# Sheet2.net
KiCad netlist of a schematic drawn in Altium Designer
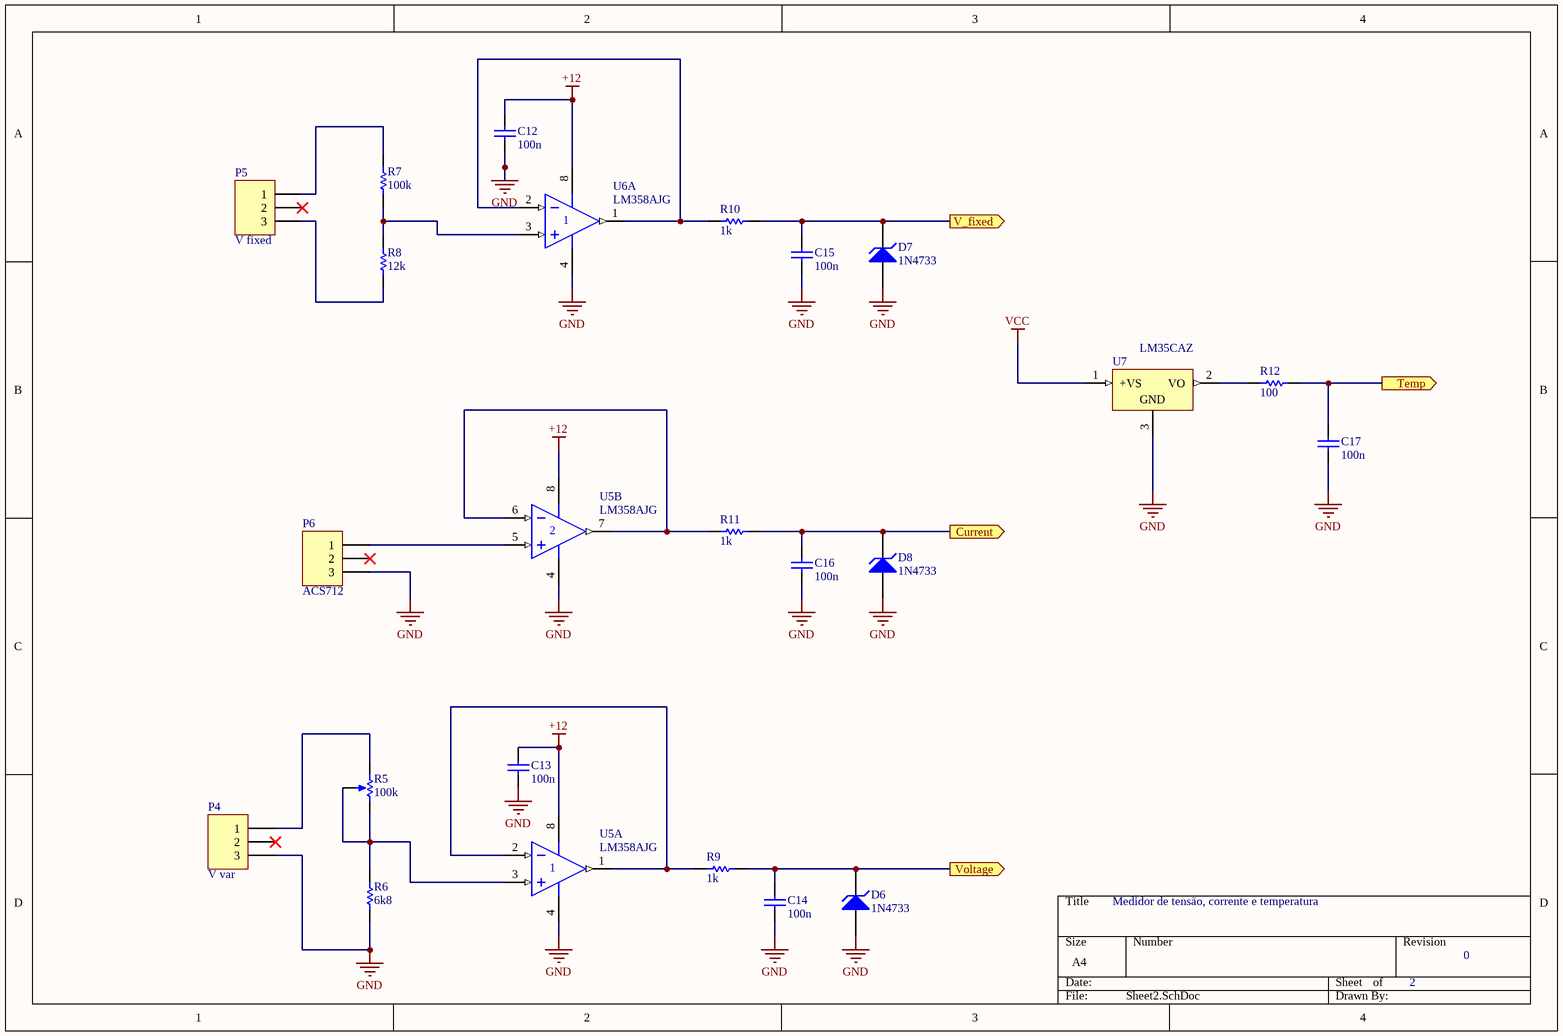
[diagram p0: Sheet2.SchDoc]

(export (version "E")
  (design (tool "Eeschema 10.0.6"))
  (components
    (comp (ref "C12")
      (value "100n")
      (footprint "RAD-0.2")
      (description "Capacitor")
      (libsource (lib "Basic Library") (part "C"))
    )
    (comp (ref "C13")
      (value "100n")
      (footprint "RAD-0.2")
      (description "Capacitor")
      (libsource (lib "Basic Library") (part "C"))
    )
    (comp (ref "C14")
      (value "100n")
      (footprint "RAD-0.2")
      (description "Capacitor")
      (libsource (lib "Basic Library") (part "C"))
    )
    (comp (ref "C15")
      (value "100n")
      (footprint "RAD-0.2")
      (description "Capacitor")
      (libsource (lib "Basic Library") (part "C"))
    )
    (comp (ref "C16")
      (value "100n")
      (footprint "RAD-0.2")
      (description "Capacitor")
      (libsource (lib "Basic Library") (part "C"))
    )
    (comp (ref "C17")
      (value "100n")
      (footprint "RAD-0.2")
      (description "Capacitor")
      (libsource (lib "Basic Library") (part "C"))
    )
    (comp (ref "D6")
      (value "1N4733")
      (footprint "DIODE-SIGNAL")
      (description "Zener Diode")
      (libsource (lib "Basic Library") (part "D Zener"))
    )
    (comp (ref "D7")
      (value "1N4733")
      (footprint "DIODE-SIGNAL")
      (description "Zener Diode")
      (libsource (lib "Basic Library") (part "D Zener"))
    )
    (comp (ref "D8")
      (value "1N4733")
      (footprint "DIODE-SIGNAL")
      (description "Zener Diode")
      (libsource (lib "Basic Library") (part "D Zener"))
    )
    (comp (ref "P4")
      (value "V var")
      (footprint "HDR1X3")
      (description "Header, 3-Pin")
      (fields (field (name "PUBLISHER") "Altium Limited"))
      (libsource (lib "Miscellaneous Connectors") (part "Header 3"))
    )
    (comp (ref "P5")
      (value "V fixed")
      (footprint "HDR1X3")
      (description "Header, 3-Pin")
      (fields (field (name "PUBLISHER") "Altium Limited"))
      (libsource (lib "Miscellaneous Connectors") (part "Header 3"))
    )
    (comp (ref "P6")
      (value "ACS712")
      (footprint "HDR1X3")
      (description "Header, 3-Pin")
      (fields (field (name "PUBLISHER") "Altium Limited"))
      (libsource (lib "Miscellaneous Connectors") (part "Header 3"))
    )
    (comp (ref "R5")
      (value "100k")
      (footprint "VR1")
      (description "Potentiometer")
      (libsource (lib "Basic Library") (part "R Pot"))
    )
    (comp (ref "R6")
      (value "6k8")
      (footprint "AXIAL-0.4")
      (description "Resistor")
      (libsource (lib "Basic Library") (part "R"))
    )
    (comp (ref "R7")
      (value "100k")
      (footprint "AXIAL-0.4")
      (description "Resistor")
      (libsource (lib "Basic Library") (part "R"))
    )
    (comp (ref "R8")
      (value "12k")
      (footprint "AXIAL-0.4")
      (description "Resistor")
      (libsource (lib "Basic Library") (part "R"))
    )
    (comp (ref "R9")
      (value "1k")
      (footprint "AXIAL-0.4")
      (description "Resistor")
      (libsource (lib "Basic Library") (part "R"))
    )
    (comp (ref "R10")
      (value "1k")
      (footprint "AXIAL-0.4")
      (description "Resistor")
      (libsource (lib "Basic Library") (part "R"))
    )
    (comp (ref "R11")
      (value "1k")
      (footprint "AXIAL-0.4")
      (description "Resistor")
      (libsource (lib "Basic Library") (part "R"))
    )
    (comp (ref "R12")
      (value "100")
      (footprint "AXIAL-0.4")
      (description "Resistor")
      (libsource (lib "Basic Library") (part "R"))
    )
    (comp (ref "U5")
      (value "LM358AJG")
      (footprint "JG008")
      (description "Dual Operational Amplifier")
      (fields (field (name "PUBLISHER") "Altium Limited"))
      (libsource (lib "TI Operational Amplifier") (part "LM358AJG"))
    )
    (comp (ref "U6")
      (value "LM358AJG")
      (footprint "JG008")
      (description "Dual Operational Amplifier")
      (fields (field (name "PUBLISHER") "Altium Limited"))
      (libsource (lib "TI Operational Amplifier") (part "LM358AJG"))
    )
    (comp (ref "U7")
      (value "LM35CAZ")
      (footprint "Z03A")
      (description "Precision Centigrade Temperature Sensor, 3-pin TO-92")
      (fields
        (field (name "MANUFACTURER") "National Semiconductor")
        (field (name "PUBLISHER") "Altium Limited")
      )
      (libsource (lib "NSC Temperature Sensor") (part "LM35CAZ"))
    )
  )
  (nets
    (net (code "1") (name "+12") (class "Default")
      (node (ref "C12") (pin "1") (pinfunction "1_1") (pintype "passive"))
      (node (ref "C13") (pin "1") (pinfunction "1_1") (pintype "passive"))
      (node (ref "U5") (pin "8") (pinfunction "V+_8") (pintype "power_in"))
      (node (ref "U6") (pin "8") (pinfunction "V+_8") (pintype "power_in"))
    )
    (net (code "2") (name "/Current") (class "Default")
      (node (ref "C16") (pin "1") (pinfunction "1_1") (pintype "passive"))
      (node (ref "D8") (pin "2") (pinfunction "K_2") (pintype "passive"))
      (node (ref "R11") (pin "2") (pinfunction "2_2") (pintype "passive"))
    )
    (net (code "3") (name "/Temp") (class "Default")
      (node (ref "C17") (pin "1") (pinfunction "1_1") (pintype "passive"))
      (node (ref "R12") (pin "2") (pinfunction "2_2") (pintype "passive"))
    )
    (net (code "4") (name "/V_fixed") (class "Default")
      (node (ref "C15") (pin "1") (pinfunction "1_1") (pintype "passive"))
      (node (ref "D7") (pin "2") (pinfunction "K_2") (pintype "passive"))
      (node (ref "R10") (pin "2") (pinfunction "2_2") (pintype "passive"))
    )
    (net (code "5") (name "/Voltage") (class "Default")
      (node (ref "C14") (pin "1") (pinfunction "1_1") (pintype "passive"))
      (node (ref "D6") (pin "2") (pinfunction "K_2") (pintype "passive"))
      (node (ref "R9") (pin "2") (pinfunction "2_2") (pintype "passive"))
    )
    (net (code "6") (name "GND") (class "Default")
      (node (ref "C12") (pin "2") (pinfunction "2_2") (pintype "passive"))
      (node (ref "C13") (pin "2") (pinfunction "2_2") (pintype "passive"))
      (node (ref "C14") (pin "2") (pinfunction "2_2") (pintype "passive"))
      (node (ref "C15") (pin "2") (pinfunction "2_2") (pintype "passive"))
      (node (ref "C16") (pin "2") (pinfunction "2_2") (pintype "passive"))
      (node (ref "C17") (pin "2") (pinfunction "2_2") (pintype "passive"))
      (node (ref "D6") (pin "1") (pinfunction "A_1") (pintype "passive"))
      (node (ref "D7") (pin "1") (pinfunction "A_1") (pintype "passive"))
      (node (ref "D8") (pin "1") (pinfunction "A_1") (pintype "passive"))
      (node (ref "P4") (pin "3") (pinfunction "3_3") (pintype "passive"))
      (node (ref "P6") (pin "3") (pinfunction "3_3") (pintype "passive"))
      (node (ref "R6") (pin "1") (pinfunction "1_1") (pintype "passive"))
      (node (ref "U5") (pin "4") (pinfunction "V-_4") (pintype "power_in"))
      (node (ref "U6") (pin "4") (pinfunction "V-_4") (pintype "power_in"))
      (node (ref "U7") (pin "3") (pinfunction "GND_3") (pintype "power_in"))
    )
    (net (code "7") (name "Net-(P5-Pad1)") (class "Default")
      (node (ref "P5") (pin "1") (pinfunction "1_1") (pintype "passive"))
      (node (ref "R7") (pin "2") (pinfunction "2_2") (pintype "passive"))
    )
    (net (code "8") (name "Net-(P5-Pad3)") (class "Default")
      (node (ref "P5") (pin "3") (pinfunction "3_3") (pintype "passive"))
      (node (ref "R8") (pin "1") (pinfunction "1_1") (pintype "passive"))
    )
    (net (code "9") (name "Net-(R5-BOT)") (class "Default")
      (node (ref "R5") (pin "2") (pinfunction "BOT_2") (pintype "passive"))
      (node (ref "R5") (pin "3") (pinfunction "TAP_3") (pintype "passive"))
      (node (ref "R6") (pin "2") (pinfunction "2_2") (pintype "passive"))
      (node (ref "U5") (pin "3") (pinfunction "IN+_3") (pintype "input"))
    )
    (net (code "10") (name "Net-(R5-TOP)") (class "Default")
      (node (ref "P4") (pin "1") (pinfunction "1_1") (pintype "passive"))
      (node (ref "R5") (pin "1") (pinfunction "TOP_1") (pintype "passive"))
    )
    (net (code "11") (name "Net-(U5A-IN-)") (class "Default")
      (node (ref "R9") (pin "1") (pinfunction "1_1") (pintype "passive"))
      (node (ref "U5") (pin "1") (pinfunction "OUT_1") (pintype "output"))
      (node (ref "U5") (pin "2") (pinfunction "IN-_2") (pintype "input"))
    )
    (net (code "12") (name "Net-(U5B-IN+)") (class "Default")
      (node (ref "P6") (pin "1") (pinfunction "1_1") (pintype "passive"))
      (node (ref "U5") (pin "5") (pinfunction "IN+_5") (pintype "input"))
    )
    (net (code "13") (name "Net-(U5B-IN-)") (class "Default")
      (node (ref "R11") (pin "1") (pinfunction "1_1") (pintype "passive"))
      (node (ref "U5") (pin "6") (pinfunction "IN-_6") (pintype "input"))
      (node (ref "U5") (pin "7") (pinfunction "OUT_7") (pintype "output"))
    )
    (net (code "14") (name "Net-(U6A-IN+)") (class "Default")
      (node (ref "R7") (pin "1") (pinfunction "1_1") (pintype "passive"))
      (node (ref "R8") (pin "2") (pinfunction "2_2") (pintype "passive"))
      (node (ref "U6") (pin "3") (pinfunction "IN+_3") (pintype "input"))
    )
    (net (code "15") (name "Net-(U6A-IN-)") (class "Default")
      (node (ref "R10") (pin "1") (pinfunction "1_1") (pintype "passive"))
      (node (ref "U6") (pin "1") (pinfunction "OUT_1") (pintype "output"))
      (node (ref "U6") (pin "2") (pinfunction "IN-_2") (pintype "input"))
    )
    (net (code "16") (name "Net-(U7-VO)") (class "Default")
      (node (ref "R12") (pin "1") (pinfunction "1_1") (pintype "passive"))
      (node (ref "U7") (pin "2") (pinfunction "VO_2") (pintype "output"))
    )
    (net (code "17") (name "VCC") (class "Default")
      (node (ref "U7") (pin "1") (pinfunction "+VS_1") (pintype "input"))
    )
    (net (code "18") (name "unconnected-(P4-Pad2)") (class "Default")
      (node (ref "P4") (pin "2") (pinfunction "2_2") (pintype "passive+no_connect"))
    )
    (net (code "19") (name "unconnected-(P5-Pad2)") (class "Default")
      (node (ref "P5") (pin "2") (pinfunction "2_2") (pintype "passive+no_connect"))
    )
    (net (code "20") (name "unconnected-(P6-Pad2)") (class "Default")
      (node (ref "P6") (pin "2") (pinfunction "2_2") (pintype "passive+no_connect"))
    )
  )
)
